# 4brar07_Buck_Boost_Module_With_Led_Matri.net
KiCad netlist of a schematic drawn in EAGLE
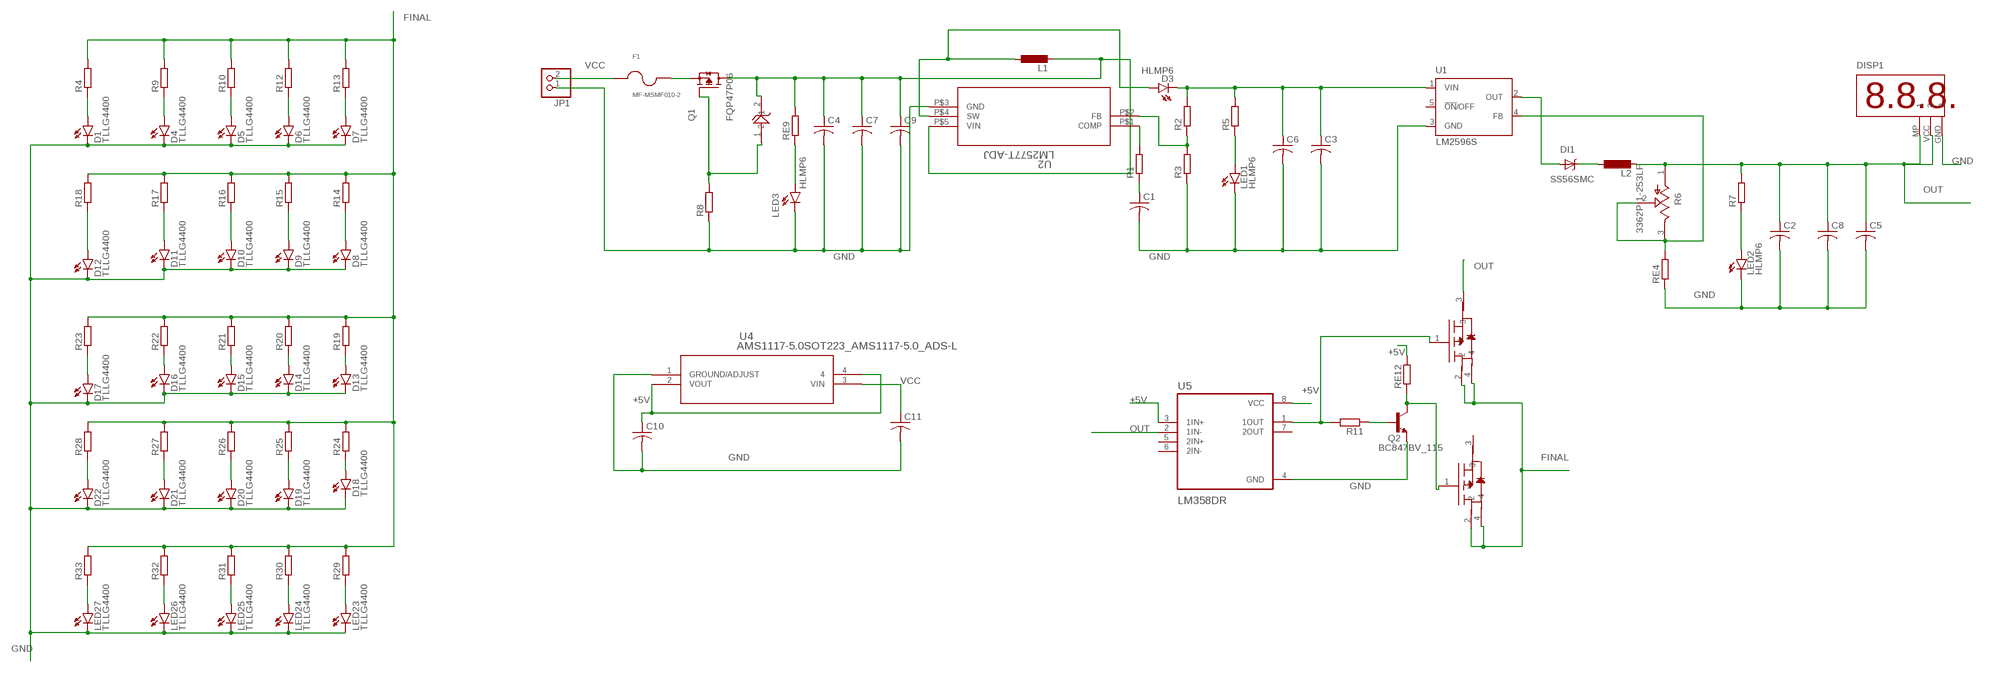
[diagram p0: schematic, sheet 1]

(export (version "E")
  (design (tool "Eeschema 10.0.6"))
  (components
    (comp (ref "C1")
      (value "C-USC0805")
      (footprint "eagle-import:C0805")
      (libsource (lib "eagle-import") (part "C-USC0805"))
    )
    (comp (ref "C2")
      (value "C-USC0805")
      (footprint "eagle-import:C0805")
      (libsource (lib "eagle-import") (part "C-USC0805"))
    )
    (comp (ref "C3")
      (value "C-USC0805")
      (footprint "eagle-import:C0805")
      (libsource (lib "eagle-import") (part "C-USC0805"))
    )
    (comp (ref "C4")
      (value "C-USC0805")
      (footprint "eagle-import:C0805")
      (libsource (lib "eagle-import") (part "C-USC0805"))
    )
    (comp (ref "C5")
      (value "C-USC0805")
      (footprint "eagle-import:C0805")
      (libsource (lib "eagle-import") (part "C-USC0805"))
    )
    (comp (ref "C6")
      (value "C-USC0805")
      (footprint "eagle-import:C0805")
      (libsource (lib "eagle-import") (part "C-USC0805"))
    )
    (comp (ref "C7")
      (value "C-USC0805")
      (footprint "eagle-import:C0805")
      (libsource (lib "eagle-import") (part "C-USC0805"))
    )
    (comp (ref "C8")
      (value "C-USC0805")
      (footprint "eagle-import:C0805")
      (libsource (lib "eagle-import") (part "C-USC0805"))
    )
    (comp (ref "C9")
      (value "C-USC0805")
      (footprint "eagle-import:C0805")
      (libsource (lib "eagle-import") (part "C-USC0805"))
    )
    (comp (ref "C10")
      (value "C-USC0805")
      (footprint "eagle-import:C0805")
      (libsource (lib "eagle-import") (part "C-USC0805"))
    )
    (comp (ref "C11")
      (value "C-USC0805")
      (footprint "eagle-import:C0805")
      (libsource (lib "eagle-import") (part "C-USC0805"))
    )
    (comp (ref "D1")
      (value "TLLG4400")
      (footprint "eagle-import:LED3MM")
      (fields (field (name "MF") "VISHAY SEMICONDUCTOR"))
      (libsource (lib "eagle-import") (part "TLLG4400"))
    )
    (comp (ref "D3")
      (value "HLMP6")
      (footprint "eagle-import:HLMP6")
      (fields (field (name "MF") "AGILENT TECHNOLOGIES") (field (name "MPN") "HLMP-6500"))
      (libsource (lib "eagle-import") (part "HLMP6"))
    )
    (comp (ref "D4")
      (value "TLLG4400")
      (footprint "eagle-import:LED3MM")
      (fields (field (name "MF") "VISHAY SEMICONDUCTOR"))
      (libsource (lib "eagle-import") (part "TLLG4400"))
    )
    (comp (ref "D5")
      (value "TLLG4400")
      (footprint "eagle-import:LED3MM")
      (fields (field (name "MF") "VISHAY SEMICONDUCTOR"))
      (libsource (lib "eagle-import") (part "TLLG4400"))
    )
    (comp (ref "D6")
      (value "TLLG4400")
      (footprint "eagle-import:LED3MM")
      (fields (field (name "MF") "VISHAY SEMICONDUCTOR"))
      (libsource (lib "eagle-import") (part "TLLG4400"))
    )
    (comp (ref "D7")
      (value "TLLG4400")
      (footprint "eagle-import:LED3MM")
      (fields (field (name "MF") "VISHAY SEMICONDUCTOR"))
      (libsource (lib "eagle-import") (part "TLLG4400"))
    )
    (comp (ref "D8")
      (value "TLLG4400")
      (footprint "eagle-import:LED3MM")
      (fields (field (name "MF") "VISHAY SEMICONDUCTOR"))
      (libsource (lib "eagle-import") (part "TLLG4400"))
    )
    (comp (ref "D9")
      (value "TLLG4400")
      (footprint "eagle-import:LED3MM")
      (fields (field (name "MF") "VISHAY SEMICONDUCTOR"))
      (libsource (lib "eagle-import") (part "TLLG4400"))
    )
    (comp (ref "D10")
      (value "TLLG4400")
      (footprint "eagle-import:LED3MM")
      (fields (field (name "MF") "VISHAY SEMICONDUCTOR"))
      (libsource (lib "eagle-import") (part "TLLG4400"))
    )
    (comp (ref "D11")
      (value "TLLG4400")
      (footprint "eagle-import:LED3MM")
      (fields (field (name "MF") "VISHAY SEMICONDUCTOR"))
      (libsource (lib "eagle-import") (part "TLLG4400"))
    )
    (comp (ref "D12")
      (value "TLLG4400")
      (footprint "eagle-import:LED3MM")
      (fields (field (name "MF") "VISHAY SEMICONDUCTOR"))
      (libsource (lib "eagle-import") (part "TLLG4400"))
    )
    (comp (ref "D13")
      (value "TLLG4400")
      (footprint "eagle-import:LED3MM")
      (fields (field (name "MF") "VISHAY SEMICONDUCTOR"))
      (libsource (lib "eagle-import") (part "TLLG4400"))
    )
    (comp (ref "D14")
      (value "TLLG4400")
      (footprint "eagle-import:LED3MM")
      (fields (field (name "MF") "VISHAY SEMICONDUCTOR"))
      (libsource (lib "eagle-import") (part "TLLG4400"))
    )
    (comp (ref "D15")
      (value "TLLG4400")
      (footprint "eagle-import:LED3MM")
      (fields (field (name "MF") "VISHAY SEMICONDUCTOR"))
      (libsource (lib "eagle-import") (part "TLLG4400"))
    )
    (comp (ref "D16")
      (value "TLLG4400")
      (footprint "eagle-import:LED3MM")
      (fields (field (name "MF") "VISHAY SEMICONDUCTOR"))
      (libsource (lib "eagle-import") (part "TLLG4400"))
    )
    (comp (ref "D17")
      (value "TLLG4400")
      (footprint "eagle-import:LED3MM")
      (fields (field (name "MF") "VISHAY SEMICONDUCTOR"))
      (libsource (lib "eagle-import") (part "TLLG4400"))
    )
    (comp (ref "D18")
      (value "TLLG4400")
      (footprint "eagle-import:LED3MM")
      (fields (field (name "MF") "VISHAY SEMICONDUCTOR"))
      (libsource (lib "eagle-import") (part "TLLG4400"))
    )
    (comp (ref "D19")
      (value "TLLG4400")
      (footprint "eagle-import:LED3MM")
      (fields (field (name "MF") "VISHAY SEMICONDUCTOR"))
      (libsource (lib "eagle-import") (part "TLLG4400"))
    )
    (comp (ref "D20")
      (value "TLLG4400")
      (footprint "eagle-import:LED3MM")
      (fields (field (name "MF") "VISHAY SEMICONDUCTOR"))
      (libsource (lib "eagle-import") (part "TLLG4400"))
    )
    (comp (ref "D21")
      (value "TLLG4400")
      (footprint "eagle-import:LED3MM")
      (fields (field (name "MF") "VISHAY SEMICONDUCTOR"))
      (libsource (lib "eagle-import") (part "TLLG4400"))
    )
    (comp (ref "D22")
      (value "TLLG4400")
      (footprint "eagle-import:LED3MM")
      (fields (field (name "MF") "VISHAY SEMICONDUCTOR"))
      (libsource (lib "eagle-import") (part "TLLG4400"))
    )
    (comp (ref "DI1")
      (value "SS56SMC")
      (footprint "eagle-import:SMC")
      (fields (field (name "MF") "MDD") (field (name "MP") "SS56"))
      (libsource (lib "eagle-import") (part "SS56SMC"))
    )
    (comp (ref "DISP1")
      (value "VOLTMETER")
      (footprint "eagle-import:VOLTMETER")
      (fields (field (name "DISP1") "DISP1"))
      (libsource (lib "eagle-import") (part "VOLTMETER"))
    )
    (comp (ref "F1")
      (value "MF-MSMF010-2")
      (footprint "eagle-import:FUSER_MF-MSMF010-2")
      (fields (field (name "MF") "Bourns"))
      (libsource (lib "eagle-import") (part "MF-MSMF010-2"))
    )
    (comp (ref "JP1")
      (value "PINHD-1X2")
      (footprint "eagle-import:1X02")
      (libsource (lib "eagle-import") (part "PINHD-1X2"))
    )
    (comp (ref "L1")
      (value "L-EUL1812")
      (footprint "eagle-import:L1812")
      (libsource (lib "eagle-import") (part "L-EUL1812"))
    )
    (comp (ref "L2")
      (value "L-EUL1812")
      (footprint "eagle-import:L1812")
      (libsource (lib "eagle-import") (part "L-EUL1812"))
    )
    (comp (ref "LED1")
      (value "HLMP6")
      (footprint "eagle-import:HLMP6")
      (fields (field (name "MF") "AGILENT TECHNOLOGIES") (field (name "MPN") "HLMP-6500"))
      (libsource (lib "eagle-import") (part "HLMP6"))
    )
    (comp (ref "LED2")
      (value "HLMP6")
      (footprint "eagle-import:HLMP6")
      (fields (field (name "MF") "AGILENT TECHNOLOGIES") (field (name "MPN") "HLMP-6500"))
      (libsource (lib "eagle-import") (part "HLMP6"))
    )
    (comp (ref "LED3")
      (value "HLMP6")
      (footprint "eagle-import:HLMP6")
      (fields (field (name "MF") "AGILENT TECHNOLOGIES") (field (name "MPN") "HLMP-6500"))
      (libsource (lib "eagle-import") (part "HLMP6"))
    )
    (comp (ref "LED23")
      (value "TLLG4400")
      (footprint "eagle-import:LED3MM")
      (fields (field (name "MF") "VISHAY SEMICONDUCTOR"))
      (libsource (lib "eagle-import") (part "TLLG4400"))
    )
    (comp (ref "LED24")
      (value "TLLG4400")
      (footprint "eagle-import:LED3MM")
      (fields (field (name "MF") "VISHAY SEMICONDUCTOR"))
      (libsource (lib "eagle-import") (part "TLLG4400"))
    )
    (comp (ref "LED25")
      (value "TLLG4400")
      (footprint "eagle-import:LED3MM")
      (fields (field (name "MF") "VISHAY SEMICONDUCTOR"))
      (libsource (lib "eagle-import") (part "TLLG4400"))
    )
    (comp (ref "LED26")
      (value "TLLG4400")
      (footprint "eagle-import:LED3MM")
      (fields (field (name "MF") "VISHAY SEMICONDUCTOR"))
      (libsource (lib "eagle-import") (part "TLLG4400"))
    )
    (comp (ref "LED27")
      (value "TLLG4400")
      (footprint "eagle-import:LED3MM")
      (fields (field (name "MF") "VISHAY SEMICONDUCTOR"))
      (libsource (lib "eagle-import") (part "TLLG4400"))
    )
    (comp (ref "Q1")
      (value "FQP47P06")
      (footprint "eagle-import:TO254P1067X483X2286-3")
      (fields (field (name "MF") "ON Semiconductor"))
      (libsource (lib "eagle-import") (part "FQP47P06"))
    )
    (comp (ref "Q2")
      (value "BC847BV_115")
      (footprint "eagle-import:SOT666")
      (libsource (lib "eagle-import") (part "BC847BV_115"))
    )
    (comp (ref "Q3")
      (value "NTF5P03T3G")
      (footprint "eagle-import:SOT230P700X175-4N")
      (libsource (lib "eagle-import") (part "NTF5P03T3G"))
    )
    (comp (ref "Q4")
      (value "NTF5P03T3G")
      (footprint "eagle-import:SOT230P700X175-4N")
      (libsource (lib "eagle-import") (part "NTF5P03T3G"))
    )
    (comp (ref "R1")
      (value "R-EU_R0805")
      (footprint "eagle-import:R0805")
      (libsource (lib "eagle-import") (part "R-EU_R0805"))
    )
    (comp (ref "R2")
      (value "R-EU_R0805")
      (footprint "eagle-import:R0805")
      (libsource (lib "eagle-import") (part "R-EU_R0805"))
    )
    (comp (ref "R3")
      (value "R-EU_R0805")
      (footprint "eagle-import:R0805")
      (libsource (lib "eagle-import") (part "R-EU_R0805"))
    )
    (comp (ref "R4")
      (value "R-EU_R0805")
      (footprint "eagle-import:R0805")
      (libsource (lib "eagle-import") (part "R-EU_R0805"))
    )
    (comp (ref "R5")
      (value "R-EU_R0805")
      (footprint "eagle-import:R0805")
      (libsource (lib "eagle-import") (part "R-EU_R0805"))
    )
    (comp (ref "R6")
      (value "3362P-1-253LF")
      (footprint "eagle-import:TRIM_3362P-1-253LF")
      (fields (field (name "MF") "Bourns"))
      (libsource (lib "eagle-import") (part "3362P-1-253LF"))
    )
    (comp (ref "R7")
      (value "R-EU_R0805")
      (footprint "eagle-import:R0805")
      (libsource (lib "eagle-import") (part "R-EU_R0805"))
    )
    (comp (ref "R8")
      (value "R-EU_R0805")
      (footprint "eagle-import:R0805")
      (libsource (lib "eagle-import") (part "R-EU_R0805"))
    )
    (comp (ref "R9")
      (value "R-EU_R0805")
      (footprint "eagle-import:R0805")
      (libsource (lib "eagle-import") (part "R-EU_R0805"))
    )
    (comp (ref "R10")
      (value "R-EU_R0805")
      (footprint "eagle-import:R0805")
      (libsource (lib "eagle-import") (part "R-EU_R0805"))
    )
    (comp (ref "R11")
      (value "R-EU_R0805")
      (footprint "eagle-import:R0805")
      (libsource (lib "eagle-import") (part "R-EU_R0805"))
    )
    (comp (ref "R12")
      (value "R-EU_R0805")
      (footprint "eagle-import:R0805")
      (libsource (lib "eagle-import") (part "R-EU_R0805"))
    )
    (comp (ref "R13")
      (value "R-EU_R0805")
      (footprint "eagle-import:R0805")
      (libsource (lib "eagle-import") (part "R-EU_R0805"))
    )
    (comp (ref "R14")
      (value "R-EU_R0805")
      (footprint "eagle-import:R0805")
      (libsource (lib "eagle-import") (part "R-EU_R0805"))
    )
    (comp (ref "R15")
      (value "R-EU_R0805")
      (footprint "eagle-import:R0805")
      (libsource (lib "eagle-import") (part "R-EU_R0805"))
    )
    (comp (ref "R16")
      (value "R-EU_R0805")
      (footprint "eagle-import:R0805")
      (libsource (lib "eagle-import") (part "R-EU_R0805"))
    )
    (comp (ref "R17")
      (value "R-EU_R0805")
      (footprint "eagle-import:R0805")
      (libsource (lib "eagle-import") (part "R-EU_R0805"))
    )
    (comp (ref "R18")
      (value "R-EU_R0805")
      (footprint "eagle-import:R0805")
      (libsource (lib "eagle-import") (part "R-EU_R0805"))
    )
    (comp (ref "R19")
      (value "R-EU_R0805")
      (footprint "eagle-import:R0805")
      (libsource (lib "eagle-import") (part "R-EU_R0805"))
    )
    (comp (ref "R20")
      (value "R-EU_R0805")
      (footprint "eagle-import:R0805")
      (libsource (lib "eagle-import") (part "R-EU_R0805"))
    )
    (comp (ref "R21")
      (value "R-EU_R0805")
      (footprint "eagle-import:R0805")
      (libsource (lib "eagle-import") (part "R-EU_R0805"))
    )
    (comp (ref "R22")
      (value "R-EU_R0805")
      (footprint "eagle-import:R0805")
      (libsource (lib "eagle-import") (part "R-EU_R0805"))
    )
    (comp (ref "R23")
      (value "R-EU_R0805")
      (footprint "eagle-import:R0805")
      (libsource (lib "eagle-import") (part "R-EU_R0805"))
    )
    (comp (ref "R24")
      (value "R-EU_R0805")
      (footprint "eagle-import:R0805")
      (libsource (lib "eagle-import") (part "R-EU_R0805"))
    )
    (comp (ref "R25")
      (value "R-EU_R0805")
      (footprint "eagle-import:R0805")
      (libsource (lib "eagle-import") (part "R-EU_R0805"))
    )
    (comp (ref "R26")
      (value "R-EU_R0805")
      (footprint "eagle-import:R0805")
      (libsource (lib "eagle-import") (part "R-EU_R0805"))
    )
    (comp (ref "R27")
      (value "R-EU_R0805")
      (footprint "eagle-import:R0805")
      (libsource (lib "eagle-import") (part "R-EU_R0805"))
    )
    (comp (ref "R28")
      (value "R-EU_R0805")
      (footprint "eagle-import:R0805")
      (libsource (lib "eagle-import") (part "R-EU_R0805"))
    )
    (comp (ref "R29")
      (value "R-EU_R0805")
      (footprint "eagle-import:R0805")
      (libsource (lib "eagle-import") (part "R-EU_R0805"))
    )
    (comp (ref "R30")
      (value "R-EU_R0805")
      (footprint "eagle-import:R0805")
      (libsource (lib "eagle-import") (part "R-EU_R0805"))
    )
    (comp (ref "R31")
      (value "R-EU_R0805")
      (footprint "eagle-import:R0805")
      (libsource (lib "eagle-import") (part "R-EU_R0805"))
    )
    (comp (ref "R32")
      (value "R-EU_R0805")
      (footprint "eagle-import:R0805")
      (libsource (lib "eagle-import") (part "R-EU_R0805"))
    )
    (comp (ref "R33")
      (value "R-EU_R0805")
      (footprint "eagle-import:R0805")
      (libsource (lib "eagle-import") (part "R-EU_R0805"))
    )
    (comp (ref "RE4")
      (value "R-EU_R0805")
      (footprint "eagle-import:R0805")
      (libsource (lib "eagle-import") (part "R-EU_R0805"))
    )
    (comp (ref "RE9")
      (value "R-EU_R0805")
      (footprint "eagle-import:R0805")
      (libsource (lib "eagle-import") (part "R-EU_R0805"))
    )
    (comp (ref "RE12")
      (value "R-EU_R0805")
      (footprint "eagle-import:R0805")
      (libsource (lib "eagle-import") (part "R-EU_R0805"))
    )
    (comp (ref "U$1")
      (value "ZMM12")
      (footprint "eagle-import:ZMM12")
      (libsource (lib "eagle-import") (part "ZMM12"))
    )
    (comp (ref "U1")
      (value "LM2596S")
      (footprint "eagle-import:TO263-5")
      (fields (field (name "MF") "NATIONAL SEMICONDUCTOR") (field (name "MPN") "LM2596S-ADJ/NOPB"))
      (libsource (lib "eagle-import") (part "LM2596S"))
    )
    (comp (ref "U2")
      (value "LM2577T-ADJ")
      (footprint "eagle-import:VREG_LM2577T-ADJ_NOPB")
      (libsource (lib "eagle-import") (part "LM2577T-ADJ"))
    )
    (comp (ref "U4")
      (value "AMS1117-5.0SOT223_AMS1117-5.0_ADS-L")
      (footprint "eagle-import:SOT223_AMS1117-5.0_ADS-L")
      (fields
        (field (name "MANUFACTURER_PART_NUMBER") "AMS1117-5.0")
        (field (name "COPYRIGHT") "Copyright (C) 2025 Ultra Librarian. All rights reserved.")
      )
      (libsource (lib "eagle-import") (part "AMS1117-5.0SOT223_AMS1117-5.0_ADS-L"))
    )
    (comp (ref "U5")
      (value "LM358DR")
      (footprint "eagle-import:SOIC127P599X175-8N")
      (fields (field (name "MF") "Rohm Semiconductor"))
      (libsource (lib "eagle-import") (part "LM358DR"))
    )
  )
  (nets
    (net (code "1") (name "/+5V") (class "Default")
      (node (ref "C10") (pin "1") (pinfunction "1_1") (pintype "passive"))
      (node (ref "RE12") (pin "2") (pinfunction "2_2") (pintype "passive"))
      (node (ref "U4") (pin "2") (pinfunction "VOUT_2") (pintype "output"))
      (node (ref "U4") (pin "4") (pinfunction "4_4") (pintype "passive"))
      (node (ref "U5") (pin "3") (pinfunction "1IN+_3") (pintype "input"))
      (node (ref "U5") (pin "8") (pinfunction "VCC_8") (pintype "power_in"))
    )
    (net (code "2") (name "/FINAL") (class "Default")
      (node (ref "Q3") (pin "2") (pinfunction "2_2") (pintype "bidirectional"))
      (node (ref "Q3") (pin "4") (pinfunction "4_4") (pintype "bidirectional"))
      (node (ref "Q4") (pin "2") (pinfunction "2_2") (pintype "bidirectional"))
      (node (ref "Q4") (pin "4") (pinfunction "4_4") (pintype "bidirectional"))
      (node (ref "R10") (pin "2") (pinfunction "2_2") (pintype "passive"))
      (node (ref "R12") (pin "2") (pinfunction "2_2") (pintype "passive"))
      (node (ref "R13") (pin "2") (pinfunction "2_2") (pintype "passive"))
      (node (ref "R14") (pin "2") (pinfunction "2_2") (pintype "passive"))
      (node (ref "R15") (pin "2") (pinfunction "2_2") (pintype "passive"))
      (node (ref "R16") (pin "2") (pinfunction "2_2") (pintype "passive"))
      (node (ref "R17") (pin "2") (pinfunction "2_2") (pintype "passive"))
      (node (ref "R18") (pin "2") (pinfunction "2_2") (pintype "passive"))
      (node (ref "R19") (pin "2") (pinfunction "2_2") (pintype "passive"))
      (node (ref "R20") (pin "2") (pinfunction "2_2") (pintype "passive"))
      (node (ref "R21") (pin "2") (pinfunction "2_2") (pintype "passive"))
      (node (ref "R22") (pin "2") (pinfunction "2_2") (pintype "passive"))
      (node (ref "R23") (pin "2") (pinfunction "2_2") (pintype "passive"))
      (node (ref "R24") (pin "2") (pinfunction "2_2") (pintype "passive"))
      (node (ref "R25") (pin "2") (pinfunction "2_2") (pintype "passive"))
      (node (ref "R26") (pin "2") (pinfunction "2_2") (pintype "passive"))
      (node (ref "R27") (pin "2") (pinfunction "2_2") (pintype "passive"))
      (node (ref "R28") (pin "2") (pinfunction "2_2") (pintype "passive"))
      (node (ref "R29") (pin "2") (pinfunction "2_2") (pintype "passive"))
      (node (ref "R30") (pin "2") (pinfunction "2_2") (pintype "passive"))
      (node (ref "R31") (pin "2") (pinfunction "2_2") (pintype "passive"))
      (node (ref "R32") (pin "2") (pinfunction "2_2") (pintype "passive"))
      (node (ref "R33") (pin "2") (pinfunction "2_2") (pintype "passive"))
      (node (ref "R4") (pin "2") (pinfunction "2_2") (pintype "passive"))
      (node (ref "R9") (pin "2") (pinfunction "2_2") (pintype "passive"))
    )
    (net (code "3") (name "/GND") (class "Default")
      (node (ref "C1") (pin "2") (pinfunction "2_2") (pintype "passive"))
      (node (ref "C10") (pin "2") (pinfunction "2_2") (pintype "passive"))
      (node (ref "C11") (pin "2") (pinfunction "2_2") (pintype "passive"))
      (node (ref "C2") (pin "2") (pinfunction "2_2") (pintype "passive"))
      (node (ref "C3") (pin "2") (pinfunction "2_2") (pintype "passive"))
      (node (ref "C4") (pin "2") (pinfunction "2_2") (pintype "passive"))
      (node (ref "C5") (pin "2") (pinfunction "2_2") (pintype "passive"))
      (node (ref "C6") (pin "2") (pinfunction "2_2") (pintype "passive"))
      (node (ref "C7") (pin "2") (pinfunction "2_2") (pintype "passive"))
      (node (ref "C8") (pin "2") (pinfunction "2_2") (pintype "passive"))
      (node (ref "C9") (pin "2") (pinfunction "2_2") (pintype "passive"))
      (node (ref "D1") (pin "K") (pinfunction "C_K") (pintype "passive"))
      (node (ref "D10") (pin "K") (pinfunction "C_K") (pintype "passive"))
      (node (ref "D11") (pin "K") (pinfunction "C_K") (pintype "passive"))
      (node (ref "D12") (pin "K") (pinfunction "C_K") (pintype "passive"))
      (node (ref "D13") (pin "K") (pinfunction "C_K") (pintype "passive"))
      (node (ref "D14") (pin "K") (pinfunction "C_K") (pintype "passive"))
      (node (ref "D15") (pin "K") (pinfunction "C_K") (pintype "passive"))
      (node (ref "D16") (pin "K") (pinfunction "C_K") (pintype "passive"))
      (node (ref "D17") (pin "K") (pinfunction "C_K") (pintype "passive"))
      (node (ref "D18") (pin "K") (pinfunction "C_K") (pintype "passive"))
      (node (ref "D19") (pin "K") (pinfunction "C_K") (pintype "passive"))
      (node (ref "D20") (pin "K") (pinfunction "C_K") (pintype "passive"))
      (node (ref "D21") (pin "K") (pinfunction "C_K") (pintype "passive"))
      (node (ref "D22") (pin "K") (pinfunction "C_K") (pintype "passive"))
      (node (ref "D4") (pin "K") (pinfunction "C_K") (pintype "passive"))
      (node (ref "D5") (pin "K") (pinfunction "C_K") (pintype "passive"))
      (node (ref "D6") (pin "K") (pinfunction "C_K") (pintype "passive"))
      (node (ref "D7") (pin "K") (pinfunction "C_K") (pintype "passive"))
      (node (ref "D8") (pin "K") (pinfunction "C_K") (pintype "passive"))
      (node (ref "D9") (pin "K") (pinfunction "C_K") (pintype "passive"))
      (node (ref "DISP1") (pin "GND") (pinfunction "3_GND") (pintype "bidirectional"))
      (node (ref "JP1") (pin "1") (pinfunction "1_1") (pintype "passive"))
      (node (ref "LED1") (pin "K") (pinfunction "K_K") (pintype "passive"))
      (node (ref "LED2") (pin "K") (pinfunction "K_K") (pintype "passive"))
      (node (ref "LED23") (pin "K") (pinfunction "C_K") (pintype "passive"))
      (node (ref "LED24") (pin "K") (pinfunction "C_K") (pintype "passive"))
      (node (ref "LED25") (pin "K") (pinfunction "C_K") (pintype "passive"))
      (node (ref "LED26") (pin "K") (pinfunction "C_K") (pintype "passive"))
      (node (ref "LED27") (pin "K") (pinfunction "C_K") (pintype "passive"))
      (node (ref "LED3") (pin "K") (pinfunction "K_K") (pintype "passive"))
      (node (ref "Q2") (pin "5") (pinfunction "5_5") (pintype "passive"))
      (node (ref "R3") (pin "1") (pinfunction "1_1") (pintype "passive"))
      (node (ref "R8") (pin "1") (pinfunction "1_1") (pintype "passive"))
      (node (ref "RE4") (pin "1") (pinfunction "1_1") (pintype "passive"))
      (node (ref "U1") (pin "3") (pinfunction "GND_3") (pintype "power_in"))
      (node (ref "U2") (pin "P$3") (pinfunction "GND_P$3") (pintype "power_in"))
      (node (ref "U4") (pin "1") (pinfunction "GROUND/ADJUST_1") (pintype "passive"))
      (node (ref "U5") (pin "4") (pinfunction "GND_4") (pintype "power_in"))
    )
    (net (code "4") (name "/OUT") (class "Default")
      (node (ref "C2") (pin "1") (pinfunction "1_1") (pintype "passive"))
      (node (ref "C5") (pin "1") (pinfunction "1_1") (pintype "passive"))
      (node (ref "C8") (pin "1") (pinfunction "1_1") (pintype "passive"))
      (node (ref "DISP1") (pin "MP") (pinfunction "1_MP") (pintype "bidirectional"))
      (node (ref "DISP1") (pin "VCC") (pinfunction "2_VCC") (pintype "bidirectional"))
      (node (ref "L2") (pin "2") (pinfunction "2_2") (pintype "passive"))
      (node (ref "Q3") (pin "3") (pinfunction "3_3") (pintype "bidirectional"))
      (node (ref "R6") (pin "1") (pinfunction "CCW_1") (pintype "passive"))
      (node (ref "R7") (pin "2") (pinfunction "2_2") (pintype "passive"))
      (node (ref "U5") (pin "2") (pinfunction "1IN-_2") (pintype "input"))
    )
    (net (code "5") (name "/VCC") (class "Default")
      (node (ref "C11") (pin "1") (pinfunction "1_1") (pintype "passive"))
      (node (ref "F1") (pin "1") (pinfunction "1_1") (pintype "passive"))
      (node (ref "JP1") (pin "2") (pinfunction "2_2") (pintype "passive"))
      (node (ref "U4") (pin "3") (pinfunction "VIN_3") (pintype "passive"))
    )
    (net (code "6") (name "Net-(C1-Pad1)") (class "Default")
      (node (ref "C1") (pin "1") (pinfunction "1_1") (pintype "passive"))
      (node (ref "R1") (pin "1") (pinfunction "1_1") (pintype "passive"))
    )
    (net (code "7") (name "Net-(D1-PadA)") (class "Default")
      (node (ref "D1") (pin "A") (pinfunction "A_A") (pintype "passive"))
      (node (ref "R4") (pin "1") (pinfunction "1_1") (pintype "passive"))
    )
    (net (code "8") (name "Net-(D4-PadA)") (class "Default")
      (node (ref "D4") (pin "A") (pinfunction "A_A") (pintype "passive"))
      (node (ref "R9") (pin "1") (pinfunction "1_1") (pintype "passive"))
    )
    (net (code "9") (name "Net-(D5-PadA)") (class "Default")
      (node (ref "D5") (pin "A") (pinfunction "A_A") (pintype "passive"))
      (node (ref "R10") (pin "1") (pinfunction "1_1") (pintype "passive"))
    )
    (net (code "10") (name "Net-(D6-PadA)") (class "Default")
      (node (ref "D6") (pin "A") (pinfunction "A_A") (pintype "passive"))
      (node (ref "R12") (pin "1") (pinfunction "1_1") (pintype "passive"))
    )
    (net (code "11") (name "Net-(D7-PadA)") (class "Default")
      (node (ref "D7") (pin "A") (pinfunction "A_A") (pintype "passive"))
      (node (ref "R13") (pin "1") (pinfunction "1_1") (pintype "passive"))
    )
    (net (code "12") (name "Net-(D8-PadA)") (class "Default")
      (node (ref "D8") (pin "A") (pinfunction "A_A") (pintype "passive"))
      (node (ref "R14") (pin "1") (pinfunction "1_1") (pintype "passive"))
    )
    (net (code "13") (name "Net-(D9-PadA)") (class "Default")
      (node (ref "D9") (pin "A") (pinfunction "A_A") (pintype "passive"))
      (node (ref "R15") (pin "1") (pinfunction "1_1") (pintype "passive"))
    )
    (net (code "14") (name "Net-(D10-PadA)") (class "Default")
      (node (ref "D10") (pin "A") (pinfunction "A_A") (pintype "passive"))
      (node (ref "R16") (pin "1") (pinfunction "1_1") (pintype "passive"))
    )
    (net (code "15") (name "Net-(D11-PadA)") (class "Default")
      (node (ref "D11") (pin "A") (pinfunction "A_A") (pintype "passive"))
      (node (ref "R17") (pin "1") (pinfunction "1_1") (pintype "passive"))
    )
    (net (code "16") (name "Net-(D12-PadA)") (class "Default")
      (node (ref "D12") (pin "A") (pinfunction "A_A") (pintype "passive"))
      (node (ref "R18") (pin "1") (pinfunction "1_1") (pintype "passive"))
    )
    (net (code "17") (name "Net-(D13-PadA)") (class "Default")
      (node (ref "D13") (pin "A") (pinfunction "A_A") (pintype "passive"))
      (node (ref "R19") (pin "1") (pinfunction "1_1") (pintype "passive"))
    )
    (net (code "18") (name "Net-(D14-PadA)") (class "Default")
      (node (ref "D14") (pin "A") (pinfunction "A_A") (pintype "passive"))
      (node (ref "R20") (pin "1") (pinfunction "1_1") (pintype "passive"))
    )
    (net (code "19") (name "Net-(D15-PadA)") (class "Default")
      (node (ref "D15") (pin "A") (pinfunction "A_A") (pintype "passive"))
      (node (ref "R21") (pin "1") (pinfunction "1_1") (pintype "passive"))
    )
    (net (code "20") (name "Net-(D16-PadA)") (class "Default")
      (node (ref "D16") (pin "A") (pinfunction "A_A") (pintype "passive"))
      (node (ref "R22") (pin "1") (pinfunction "1_1") (pintype "passive"))
    )
    (net (code "21") (name "Net-(D17-PadA)") (class "Default")
      (node (ref "D17") (pin "A") (pinfunction "A_A") (pintype "passive"))
      (node (ref "R23") (pin "1") (pinfunction "1_1") (pintype "passive"))
    )
    (net (code "22") (name "Net-(D18-PadA)") (class "Default")
      (node (ref "D18") (pin "A") (pinfunction "A_A") (pintype "passive"))
      (node (ref "R24") (pin "1") (pinfunction "1_1") (pintype "passive"))
    )
    (net (code "23") (name "Net-(D19-PadA)") (class "Default")
      (node (ref "D19") (pin "A") (pinfunction "A_A") (pintype "passive"))
      (node (ref "R25") (pin "1") (pinfunction "1_1") (pintype "passive"))
    )
    (net (code "24") (name "Net-(D20-PadA)") (class "Default")
      (node (ref "D20") (pin "A") (pinfunction "A_A") (pintype "passive"))
      (node (ref "R26") (pin "1") (pinfunction "1_1") (pintype "passive"))
    )
    (net (code "25") (name "Net-(D21-PadA)") (class "Default")
      (node (ref "D21") (pin "A") (pinfunction "A_A") (pintype "passive"))
      (node (ref "R27") (pin "1") (pinfunction "1_1") (pintype "passive"))
    )
    (net (code "26") (name "Net-(D22-PadA)") (class "Default")
      (node (ref "D22") (pin "A") (pinfunction "A_A") (pintype "passive"))
      (node (ref "R28") (pin "1") (pinfunction "1_1") (pintype "passive"))
    )
    (net (code "27") (name "Net-(DI1-PadC)") (class "Default")
      (node (ref "DI1") (pin "C") (pinfunction "C_C") (pintype "passive"))
      (node (ref "L2") (pin "1") (pinfunction "1_1") (pintype "passive"))
    )
    (net (code "28") (name "Net-(LED1-PadA)") (class "Default")
      (node (ref "LED1") (pin "A") (pinfunction "A_A") (pintype "passive"))
      (node (ref "R5") (pin "1") (pinfunction "1_1") (pintype "passive"))
    )
    (net (code "29") (name "Net-(LED2-PadA)") (class "Default")
      (node (ref "LED2") (pin "A") (pinfunction "A_A") (pintype "passive"))
      (node (ref "R7") (pin "1") (pinfunction "1_1") (pintype "passive"))
    )
    (net (code "30") (name "Net-(LED3-PadA)") (class "Default")
      (node (ref "LED3") (pin "A") (pinfunction "A_A") (pintype "passive"))
      (node (ref "RE9") (pin "1") (pinfunction "1_1") (pintype "passive"))
    )
    (net (code "31") (name "Net-(LED23-PadA)") (class "Default")
      (node (ref "LED23") (pin "A") (pinfunction "A_A") (pintype "passive"))
      (node (ref "R29") (pin "1") (pinfunction "1_1") (pintype "passive"))
    )
    (net (code "32") (name "Net-(LED24-PadA)") (class "Default")
      (node (ref "LED24") (pin "A") (pinfunction "A_A") (pintype "passive"))
      (node (ref "R30") (pin "1") (pinfunction "1_1") (pintype "passive"))
    )
    (net (code "33") (name "Net-(LED25-PadA)") (class "Default")
      (node (ref "LED25") (pin "A") (pinfunction "A_A") (pintype "passive"))
      (node (ref "R31") (pin "1") (pinfunction "1_1") (pintype "passive"))
    )
    (net (code "34") (name "Net-(LED26-PadA)") (class "Default")
      (node (ref "LED26") (pin "A") (pinfunction "A_A") (pintype "passive"))
      (node (ref "R32") (pin "1") (pinfunction "1_1") (pintype "passive"))
    )
    (net (code "35") (name "Net-(LED27-PadA)") (class "Default")
      (node (ref "LED27") (pin "A") (pinfunction "A_A") (pintype "passive"))
      (node (ref "R33") (pin "1") (pinfunction "1_1") (pintype "passive"))
    )
    (net (code "36") (name "Net-(Q1-D)") (class "Default")
      (node (ref "C4") (pin "1") (pinfunction "1_1") (pintype "passive"))
      (node (ref "C7") (pin "1") (pinfunction "1_1") (pintype "passive"))
      (node (ref "C9") (pin "1") (pinfunction "1_1") (pintype "passive"))
      (node (ref "L1") (pin "2") (pinfunction "2_2") (pintype "passive"))
      (node (ref "Q1") (pin "2") (pinfunction "D_2") (pintype "passive"))
      (node (ref "RE9") (pin "2") (pinfunction "2_2") (pintype "passive"))
      (node (ref "U$1") (pin "2") (pinfunction "2_2") (pintype "bidirectional"))
      (node (ref "U2") (pin "P$5") (pinfunction "VIN_P$5") (pintype "passive"))
    )
    (net (code "37") (name "Net-(Q1-G)") (class "Default")
      (node (ref "Q1") (pin "1") (pinfunction "G_1") (pintype "passive"))
      (node (ref "R8") (pin "2") (pinfunction "2_2") (pintype "passive"))
      (node (ref "U$1") (pin "1") (pinfunction "1_1") (pintype "bidirectional"))
    )
    (net (code "38") (name "Net-(Q1-S)") (class "Default")
      (node (ref "F1") (pin "2") (pinfunction "2_2") (pintype "passive"))
      (node (ref "Q1") (pin "3") (pinfunction "S_3") (pintype "passive"))
    )
    (net (code "39") (name "Net-(Q2-Pad1)") (class "Default")
      (node (ref "Q2") (pin "1") (pinfunction "1_1") (pintype "passive"))
      (node (ref "R11") (pin "1") (pinfunction "1_1") (pintype "passive"))
    )
    (net (code "40") (name "Net-(Q2-Pad3)") (class "Default")
      (node (ref "Q2") (pin "3") (pinfunction "3_3") (pintype "passive"))
      (node (ref "Q4") (pin "1") (pinfunction "1_1") (pintype "bidirectional"))
      (node (ref "RE12") (pin "1") (pinfunction "1_1") (pintype "passive"))
    )
    (net (code "41") (name "Net-(R6-CW)") (class "Default")
      (node (ref "R6") (pin "2") (pinfunction "WIPER_2") (pintype "passive"))
      (node (ref "R6") (pin "3") (pinfunction "CW_3") (pintype "passive"))
      (node (ref "RE4") (pin "2") (pinfunction "2_2") (pintype "passive"))
      (node (ref "U1") (pin "4") (pinfunction "FB_4") (pintype "input"))
    )
    (net (code "42") (name "Net-(U1-OUT)") (class "Default")
      (node (ref "DI1") (pin "A") (pinfunction "A_A") (pintype "passive"))
      (node (ref "U1") (pin "2") (pinfunction "OUT_2") (pintype "output"))
    )
    (net (code "43") (name "Net-(U1-VIN)") (class "Default")
      (node (ref "C3") (pin "1") (pinfunction "1_1") (pintype "passive"))
      (node (ref "C6") (pin "1") (pinfunction "1_1") (pintype "passive"))
      (node (ref "D3") (pin "K") (pinfunction "K_K") (pintype "passive"))
      (node (ref "R2") (pin "2") (pinfunction "2_2") (pintype "passive"))
      (node (ref "R5") (pin "2") (pinfunction "2_2") (pintype "passive"))
      (node (ref "U1") (pin "1") (pinfunction "VIN_1") (pintype "input"))
    )
    (net (code "44") (name "Net-(U2-COMP)") (class "Default")
      (node (ref "R1") (pin "2") (pinfunction "2_2") (pintype "passive"))
      (node (ref "U2") (pin "P$1") (pinfunction "COMP_P$1") (pintype "passive"))
    )
    (net (code "45") (name "Net-(U2-FB)") (class "Default")
      (node (ref "R2") (pin "1") (pinfunction "1_1") (pintype "passive"))
      (node (ref "R3") (pin "2") (pinfunction "2_2") (pintype "passive"))
      (node (ref "U2") (pin "P$2") (pinfunction "FB_P$2") (pintype "passive"))
    )
    (net (code "46") (name "Net-(U2-SW)") (class "Default")
      (node (ref "D3") (pin "A") (pinfunction "A_A") (pintype "passive"))
      (node (ref "L1") (pin "1") (pinfunction "1_1") (pintype "passive"))
      (node (ref "U2") (pin "P$4") (pinfunction "SW_P$4") (pintype "passive"))
    )
    (net (code "47") (name "Net-(U5-1OUT)") (class "Default")
      (node (ref "Q3") (pin "1") (pinfunction "1_1") (pintype "bidirectional"))
      (node (ref "R11") (pin "2") (pinfunction "2_2") (pintype "passive"))
      (node (ref "U5") (pin "1") (pinfunction "1OUT_1") (pintype "output"))
    )
    (net (code "48") (name "unconnected-(Q4-Pad3)") (class "Default")
      (node (ref "Q4") (pin "3") (pinfunction "3_3") (pintype "bidirectional"))
    )
    (net (code "49") (name "unconnected-(U1-~{ON}{slash}OFF-Pad5)") (class "Default")
      (node (ref "U1") (pin "5") (pinfunction "~{ON}/OFF_5") (pintype "input"))
    )
    (net (code "50") (name "unconnected-(U5-2IN+-Pad5)") (class "Default")
      (node (ref "U5") (pin "5") (pinfunction "2IN+_5") (pintype "input"))
    )
    (net (code "51") (name "unconnected-(U5-2IN--Pad6)") (class "Default")
      (node (ref "U5") (pin "6") (pinfunction "2IN-_6") (pintype "input"))
    )
    (net (code "52") (name "unconnected-(U5-2OUT-Pad7)") (class "Default")
      (node (ref "U5") (pin "7") (pinfunction "2OUT_7") (pintype "output"))
    )
  )
)
